# STM32WB55_Main_MCU.net
KiCad netlist of a schematic drawn in Altium Designer
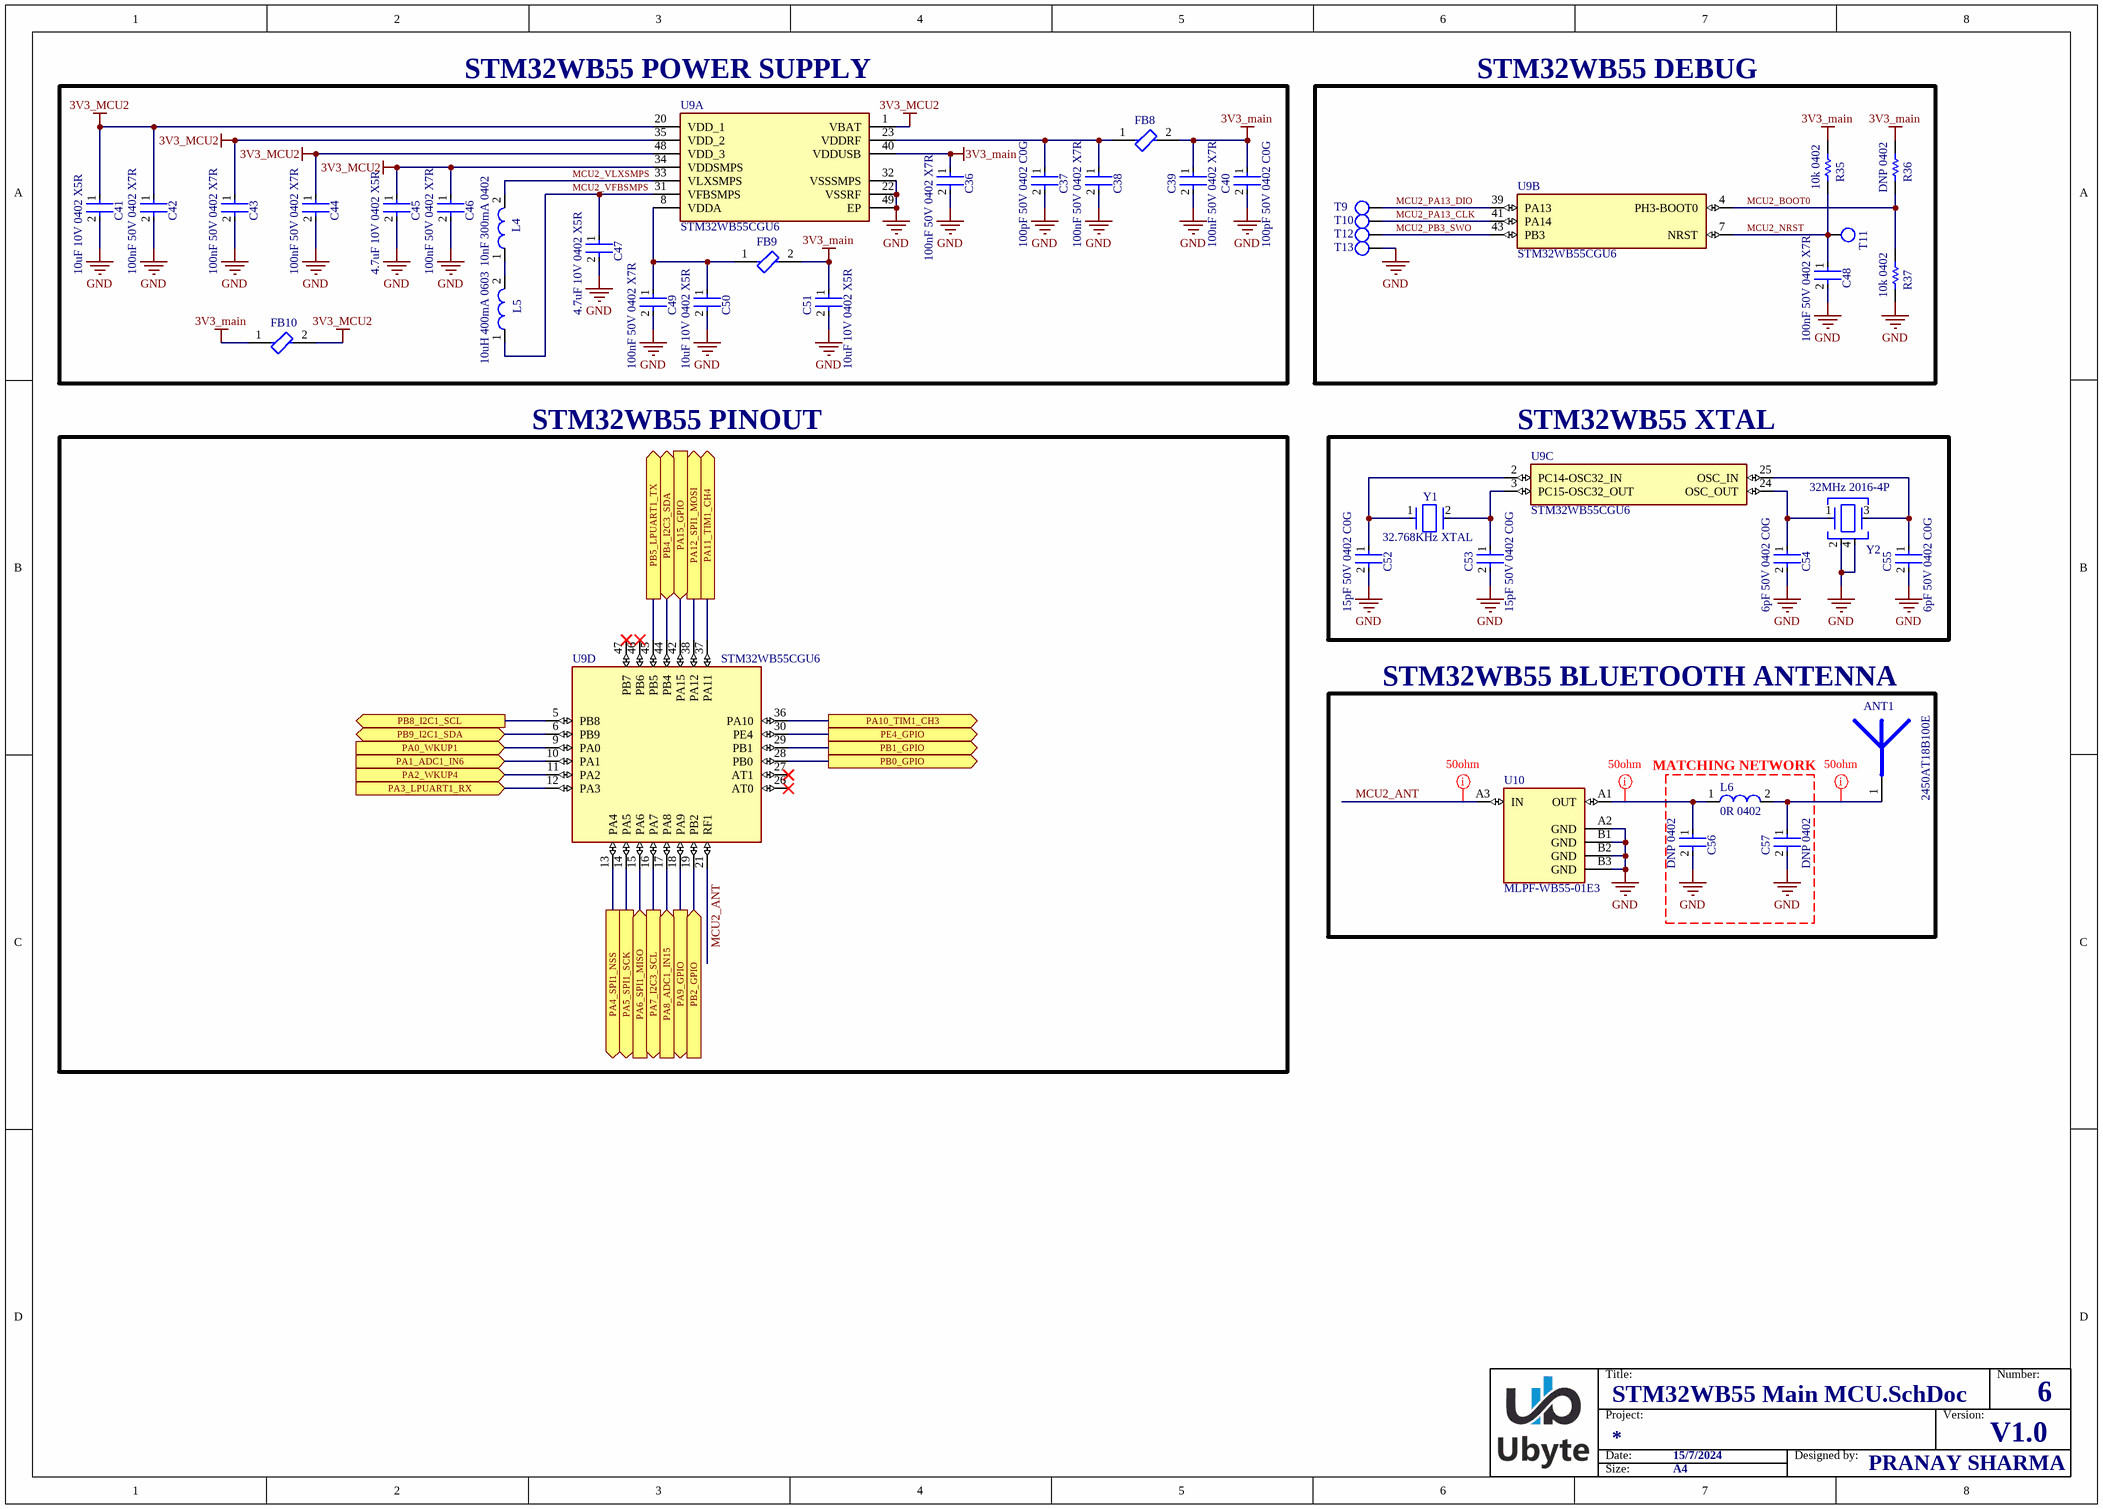
[diagram p0: STM32WB55 Main MCU.SchDoc]

(export (version "E")
  (design (tool "Eeschema 10.0.6"))
  (components
    (comp (ref "ANT1")
      (value "2450AT18B100E")
      (footprint "Miscellaneous_Lib:2450AT18B100E IPC-C")
      (libsource (lib "Miscellaneous_Lib") (part "2450AT18B100E"))
    )
    (comp (ref "C36")
      (value "100nF 50V 0402 X7R")
      (footprint "Res, Cap, Ind, LED, FB_Lib:0402 IPC CLASS C CAPACITOR")
      (libsource (lib "Capacitor_Lib") (part "100nF 50V 0402 X7R"))
    )
    (comp (ref "C37")
      (value "100pF 50V 0402 C0G")
      (footprint "Res, Cap, Ind, LED, FB_Lib:0402 IPC CLASS C CAPACITOR")
      (libsource (lib "Capacitor_Lib") (part "100pF 50V 0402 C0G"))
    )
    (comp (ref "C38")
      (value "100nF 50V 0402 X7R")
      (footprint "Res, Cap, Ind, LED, FB_Lib:0402 IPC CLASS C CAPACITOR")
      (libsource (lib "Capacitor_Lib") (part "100nF 50V 0402 X7R"))
    )
    (comp (ref "C39")
      (value "100nF 50V 0402 X7R")
      (footprint "Res, Cap, Ind, LED, FB_Lib:0402 IPC CLASS C CAPACITOR")
      (libsource (lib "Capacitor_Lib") (part "100nF 50V 0402 X7R"))
    )
    (comp (ref "C40")
      (value "100pF 50V 0402 C0G")
      (footprint "Res, Cap, Ind, LED, FB_Lib:0402 IPC CLASS C CAPACITOR")
      (libsource (lib "Capacitor_Lib") (part "100pF 50V 0402 C0G"))
    )
    (comp (ref "C41")
      (value "10uF 10V 0402 X5R")
      (footprint "Res, Cap, Ind, LED, FB_Lib:0402 IPC CLASS C CAPACITOR")
      (libsource (lib "Capacitor_Lib") (part "10uF 10V 0402 X5R"))
    )
    (comp (ref "C42")
      (value "100nF 50V 0402 X7R")
      (footprint "Res, Cap, Ind, LED, FB_Lib:0402 IPC CLASS C CAPACITOR")
      (libsource (lib "Capacitor_Lib") (part "100nF 50V 0402 X7R"))
    )
    (comp (ref "C43")
      (value "100nF 50V 0402 X7R")
      (footprint "Res, Cap, Ind, LED, FB_Lib:0402 IPC CLASS C CAPACITOR")
      (libsource (lib "Capacitor_Lib") (part "100nF 50V 0402 X7R"))
    )
    (comp (ref "C44")
      (value "100nF 50V 0402 X7R")
      (footprint "Res, Cap, Ind, LED, FB_Lib:0402 IPC CLASS C CAPACITOR")
      (libsource (lib "Capacitor_Lib") (part "100nF 50V 0402 X7R"))
    )
    (comp (ref "C45")
      (value "4.7uF 10V 0402 X5R")
      (footprint "Res, Cap, Ind, LED, FB_Lib:0402 IPC CLASS C CAPACITOR")
      (libsource (lib "Capacitor_Lib") (part "4.7uF 10V 0402 X5R"))
    )
    (comp (ref "C46")
      (value "100nF 50V 0402 X7R")
      (footprint "Res, Cap, Ind, LED, FB_Lib:0402 IPC CLASS C CAPACITOR")
      (libsource (lib "Capacitor_Lib") (part "100nF 50V 0402 X7R"))
    )
    (comp (ref "C47")
      (value "4.7uF 10V 0402 X5R")
      (footprint "Res, Cap, Ind, LED, FB_Lib:0402 IPC CLASS C CAPACITOR")
      (libsource (lib "Capacitor_Lib") (part "4.7uF 10V 0402 X5R"))
    )
    (comp (ref "C48")
      (value "100nF 50V 0402 X7R")
      (footprint "Res, Cap, Ind, LED, FB_Lib:0402 IPC CLASS C CAPACITOR")
      (libsource (lib "Capacitor_Lib") (part "100nF 50V 0402 X7R"))
    )
    (comp (ref "C49")
      (value "100nF 50V 0402 X7R")
      (footprint "Res, Cap, Ind, LED, FB_Lib:0402 IPC CLASS C CAPACITOR")
      (libsource (lib "Capacitor_Lib") (part "100nF 50V 0402 X7R"))
    )
    (comp (ref "C50")
      (value "10uF 10V 0402 X5R")
      (footprint "Res, Cap, Ind, LED, FB_Lib:0402 IPC CLASS C CAPACITOR")
      (libsource (lib "Capacitor_Lib") (part "10uF 10V 0402 X5R"))
    )
    (comp (ref "C51")
      (value "10uF 10V 0402 X5R")
      (footprint "Res, Cap, Ind, LED, FB_Lib:0402 IPC CLASS C CAPACITOR")
      (libsource (lib "Capacitor_Lib") (part "10uF 10V 0402 X5R"))
    )
    (comp (ref "C52")
      (value "15pF 50V 0402 C0G")
      (footprint "Res, Cap, Ind, LED, FB_Lib:0402 IPC CLASS C CAPACITOR")
      (libsource (lib "Capacitor_Lib") (part "15pF 50V 0402 C0G"))
    )
    (comp (ref "C53")
      (value "15pF 50V 0402 C0G")
      (footprint "Res, Cap, Ind, LED, FB_Lib:0402 IPC CLASS C CAPACITOR")
      (libsource (lib "Capacitor_Lib") (part "15pF 50V 0402 C0G"))
    )
    (comp (ref "C54")
      (value "6pF 50V 0402 C0G")
      (footprint "Res, Cap, Ind, LED, FB_Lib:0402 IPC CLASS C CAPACITOR")
      (libsource (lib "Capacitor_Lib") (part "6pF 50V 0402 C0G"))
    )
    (comp (ref "C55")
      (value "6pF 50V 0402 C0G")
      (footprint "Res, Cap, Ind, LED, FB_Lib:0402 IPC CLASS C CAPACITOR")
      (libsource (lib "Capacitor_Lib") (part "6pF 50V 0402 C0G"))
    )
    (comp (ref "C56")
      (value "DNP 0402")
      (footprint "Res, Cap, Ind, LED, FB_Lib:0402 IPC CLASS C CAPACITOR")
      (libsource (lib "Capacitor_Lib") (part "100nF 50V 0402 X7R"))
    )
    (comp (ref "C57")
      (value "DNP 0402")
      (footprint "Res, Cap, Ind, LED, FB_Lib:0402 IPC CLASS C CAPACITOR")
      (libsource (lib "Capacitor_Lib") (part "100nF 50V 0402 X7R"))
    )
    (comp (ref "FB8")
      (value "BLM15AX102SN1D")
      (footprint "Res, Cap, Ind, LED, FB_Lib:0402 IPC CLASS C FERRITE BEAD")
      (libsource (lib "Ferrite_Bead_Lib") (part "BLM15AX102SN1D"))
    )
    (comp (ref "FB9")
      (value "BLM15AX102SN1D")
      (footprint "Res, Cap, Ind, LED, FB_Lib:0402 IPC CLASS C FERRITE BEAD")
      (libsource (lib "Ferrite_Bead_Lib") (part "BLM15AX102SN1D"))
    )
    (comp (ref "FB10")
      (value "BLM15AX102SN1D")
      (footprint "Res, Cap, Ind, LED, FB_Lib:0402 IPC CLASS C FERRITE BEAD")
      (libsource (lib "Ferrite_Bead_Lib") (part "BLM15AX102SN1D"))
    )
    (comp (ref "L4")
      (value "10nF 300mA 0402")
      (footprint "Res, Cap, Ind, LED, FB_Lib:0402 IPC CLASS C FERRITE BEAD")
      (libsource (lib "Inductor_Lib") (part "SDCL1005C10NJTDF"))
    )
    (comp (ref "L5")
      (value "10uH 400mA 0603")
      (footprint "Res, Cap, Ind, LED, FB_Lib:0603 IPC CLASS C INDUCTOR")
      (libsource (lib "Inductor_Lib") (part "MGFL1608F100MT-LF"))
    )
    (comp (ref "L6")
      (value "0R 0402")
      (footprint "Res, Cap, Ind, LED, FB_Lib:0402 IPC CLASS C FERRITE BEAD")
      (libsource (lib "Inductor_Lib") (part "SDCL1005C10NJTDF"))
    )
    (comp (ref "R35")
      (value "10k 0402")
      (footprint "Res, Cap, Ind, LED, FB_Lib:0402 IPC CLASS C RESISTOR")
      (libsource (lib "Resistor_Lib") (part "10k 1% 0402"))
    )
    (comp (ref "R36")
      (value "DNP 0402")
      (footprint "Res, Cap, Ind, LED, FB_Lib:0402 IPC CLASS C RESISTOR")
      (libsource (lib "Resistor_Lib") (part "0R 1% 0402"))
    )
    (comp (ref "R37")
      (value "10k 0402")
      (footprint "Res, Cap, Ind, LED, FB_Lib:0402 IPC CLASS C RESISTOR")
      (libsource (lib "Resistor_Lib") (part "10k 1% 0402"))
    )
    (comp (ref "T9")
      (value "Test Point TH")
      (footprint "Miscellaneous_Lib:Test Point TH")
      (libsource (lib "Miscellaneous_Lib") (part "Test Point TH"))
    )
    (comp (ref "T10")
      (value "Test Point TH")
      (footprint "Miscellaneous_Lib:Test Point TH")
      (libsource (lib "Miscellaneous_Lib") (part "Test Point TH"))
    )
    (comp (ref "T11")
      (value "Test Point TH")
      (footprint "Miscellaneous_Lib:Test Point TH")
      (libsource (lib "Miscellaneous_Lib") (part "Test Point TH"))
    )
    (comp (ref "T12")
      (value "Test Point TH")
      (footprint "Miscellaneous_Lib:Test Point TH")
      (libsource (lib "Miscellaneous_Lib") (part "Test Point TH"))
    )
    (comp (ref "T13")
      (value "Test Point TH")
      (footprint "Miscellaneous_Lib:Test Point TH")
      (libsource (lib "Miscellaneous_Lib") (part "Test Point TH"))
    )
    (comp (ref "U9")
      (value "STM32WB55CGU6")
      (footprint "MCU_MPU_Lib:UFQFPN48 IPC-C")
      (libsource (lib "MCU_MPU_Lib") (part "STM32WB55CGU6"))
    )
    (comp (ref "U10")
      (value "MLPF-WB55-01E3")
      (footprint "Miscellaneous_Lib:MLPF-WB55-01E3")
      (libsource (lib "Miscellaneous_Lib") (part "MLPF-WB55-01E3"))
    )
    (comp (ref "Y1")
      (value "32.768KHz XTAL")
      (footprint "Crystals_and_Oscillators_Lib:SMD3215-2P IPC-C")
      (libsource (lib "Crystals_and_Oscillators_Lib") (part "H31003271C2070CY"))
    )
    (comp (ref "Y2")
      (value "32MHz 2016-4P")
      (footprint "Crystals_and_Oscillators_Lib:SMD2016-4P IPC-C")
      (libsource (lib "Crystals_and_Oscillators_Lib") (part "32MHz 2016-4P"))
    )
  )
  (nets
    (net (code "1") (name "/MCU2_ANT") (class "Default")
      (node (ref "U10") (pin "A3") (pinfunction "IN_A3") (pintype "bidirectional"))
      (node (ref "U9") (pin "21") (pinfunction "RF1_21") (pintype "bidirectional"))
    )
    (net (code "2") (name "/MCU2_BOOT0") (class "Default")
      (node (ref "R36") (pin "1") (pinfunction "1_1") (pintype "passive"))
      (node (ref "R37") (pin "2") (pinfunction "2_2") (pintype "passive"))
      (node (ref "U9") (pin "4") (pinfunction "PH3-BOOT0_4") (pintype "bidirectional"))
    )
    (net (code "3") (name "/MCU2_NRST") (class "Default")
      (node (ref "C48") (pin "1") (pinfunction "1_1") (pintype "passive"))
      (node (ref "R35") (pin "1") (pinfunction "1_1") (pintype "passive"))
      (node (ref "T11") (pin "0") (pinfunction "0_0") (pintype "passive"))
      (node (ref "U9") (pin "7") (pinfunction "NRST_7") (pintype "bidirectional"))
    )
    (net (code "4") (name "/MCU2_PA13_CLK") (class "Default")
      (node (ref "T10") (pin "0") (pinfunction "0_0") (pintype "passive"))
      (node (ref "U9") (pin "41") (pinfunction "PA14_41") (pintype "bidirectional"))
    )
    (net (code "5") (name "/MCU2_PA13_DIO") (class "Default")
      (node (ref "T9") (pin "0") (pinfunction "0_0") (pintype "passive"))
      (node (ref "U9") (pin "39") (pinfunction "PA13_39") (pintype "bidirectional"))
    )
    (net (code "6") (name "/MCU2_PB3_SWO") (class "Default")
      (node (ref "T12") (pin "0") (pinfunction "0_0") (pintype "passive"))
      (node (ref "U9") (pin "43") (pinfunction "PB3_43") (pintype "bidirectional"))
    )
    (net (code "7") (name "/MCU2_VFBSMPS") (class "Default")
      (node (ref "C47") (pin "1") (pinfunction "1_1") (pintype "passive"))
      (node (ref "L5") (pin "1") (pinfunction "1_1") (pintype "passive"))
      (node (ref "U9") (pin "31") (pinfunction "VFBSMPS_31") (pintype "power_in"))
    )
    (net (code "8") (name "/MCU2_VLXSMPS") (class "Default")
      (node (ref "L4") (pin "2") (pinfunction "2_2") (pintype "passive"))
      (node (ref "U9") (pin "33") (pinfunction "VLXSMPS_33") (pintype "power_in"))
    )
    (net (code "9") (name "/PA0_WKUP1") (class "Default")
      (node (ref "U9") (pin "9") (pinfunction "PA0_9") (pintype "bidirectional"))
    )
    (net (code "10") (name "/PA1_ADC1_IN6") (class "Default")
      (node (ref "U9") (pin "10") (pinfunction "PA1_10") (pintype "bidirectional"))
    )
    (net (code "11") (name "/PA2_WKUP4") (class "Default")
      (node (ref "U9") (pin "11") (pinfunction "PA2_11") (pintype "bidirectional"))
    )
    (net (code "12") (name "/PA3_LPUART1_RX") (class "Default")
      (node (ref "U9") (pin "12") (pinfunction "PA3_12") (pintype "bidirectional"))
    )
    (net (code "13") (name "/PA4_SPI1_NSS") (class "Default")
      (node (ref "U9") (pin "13") (pinfunction "PA4_13") (pintype "bidirectional"))
    )
    (net (code "14") (name "/PA5_SPI1_SCK") (class "Default")
      (node (ref "U9") (pin "14") (pinfunction "PA5_14") (pintype "bidirectional"))
    )
    (net (code "15") (name "/PA6_SPI1_MISO") (class "Default")
      (node (ref "U9") (pin "15") (pinfunction "PA6_15") (pintype "bidirectional"))
    )
    (net (code "16") (name "/PA7_I2C3_SCL") (class "Default")
      (node (ref "U9") (pin "16") (pinfunction "PA7_16") (pintype "bidirectional"))
    )
    (net (code "17") (name "/PA8_ADC1_IN15") (class "Default")
      (node (ref "U9") (pin "17") (pinfunction "PA8_17") (pintype "bidirectional"))
    )
    (net (code "18") (name "/PA9_GPIO") (class "Default")
      (node (ref "U9") (pin "18") (pinfunction "PA9_18") (pintype "bidirectional"))
    )
    (net (code "19") (name "/PA10_TIM1_CH3") (class "Default")
      (node (ref "U9") (pin "36") (pinfunction "PA10_36") (pintype "bidirectional"))
    )
    (net (code "20") (name "/PA11_TIM1_CH4") (class "Default")
      (node (ref "U9") (pin "37") (pinfunction "PA11_37") (pintype "bidirectional"))
    )
    (net (code "21") (name "/PA12_SPI1_MOSI") (class "Default")
      (node (ref "U9") (pin "38") (pinfunction "PA12_38") (pintype "bidirectional"))
    )
    (net (code "22") (name "/PA15_GPIO") (class "Default")
      (node (ref "U9") (pin "42") (pinfunction "PA15_42") (pintype "bidirectional"))
    )
    (net (code "23") (name "/PB0_GPIO") (class "Default")
      (node (ref "U9") (pin "28") (pinfunction "PB0_28") (pintype "bidirectional"))
    )
    (net (code "24") (name "/PB1_GPIO") (class "Default")
      (node (ref "U9") (pin "29") (pinfunction "PB1_29") (pintype "bidirectional"))
    )
    (net (code "25") (name "/PB2_GPIO") (class "Default")
      (node (ref "U9") (pin "19") (pinfunction "PB2_19") (pintype "bidirectional"))
    )
    (net (code "26") (name "/PB4_I2C3_SDA") (class "Default")
      (node (ref "U9") (pin "44") (pinfunction "PB4_44") (pintype "bidirectional"))
    )
    (net (code "27") (name "/PB5_LPUART1_TX") (class "Default")
      (node (ref "U9") (pin "45") (pinfunction "PB5_45") (pintype "bidirectional"))
    )
    (net (code "28") (name "/PB8_I2C1_SCL") (class "Default")
      (node (ref "U9") (pin "5") (pinfunction "PB8_5") (pintype "bidirectional"))
    )
    (net (code "29") (name "/PB9_I2C1_SDA") (class "Default")
      (node (ref "U9") (pin "6") (pinfunction "PB9_6") (pintype "bidirectional"))
    )
    (net (code "30") (name "/PE4_GPIO") (class "Default")
      (node (ref "U9") (pin "30") (pinfunction "PE4_30") (pintype "bidirectional"))
    )
    (net (code "31") (name "3V3_MCU2") (class "Default")
      (node (ref "C41") (pin "1") (pinfunction "1_1") (pintype "passive"))
      (node (ref "C42") (pin "1") (pinfunction "1_1") (pintype "passive"))
      (node (ref "C43") (pin "1") (pinfunction "1_1") (pintype "passive"))
      (node (ref "C44") (pin "1") (pinfunction "1_1") (pintype "passive"))
      (node (ref "C45") (pin "1") (pinfunction "1_1") (pintype "passive"))
      (node (ref "C46") (pin "1") (pinfunction "1_1") (pintype "passive"))
      (node (ref "FB10") (pin "2") (pinfunction "2_2") (pintype "passive"))
      (node (ref "U9") (pin "1") (pinfunction "VBAT_1") (pintype "power_in"))
      (node (ref "U9") (pin "20") (pinfunction "VDD_1_20") (pintype "power_in"))
      (node (ref "U9") (pin "34") (pinfunction "VDDSMPS_34") (pintype "power_in"))
      (node (ref "U9") (pin "35") (pinfunction "VDD_2_35") (pintype "power_in"))
      (node (ref "U9") (pin "48") (pinfunction "VDD_3_48") (pintype "power_in"))
    )
    (net (code "32") (name "3V3_main") (class "Default")
      (node (ref "C36") (pin "1") (pinfunction "1_1") (pintype "passive"))
      (node (ref "C39") (pin "1") (pinfunction "1_1") (pintype "passive"))
      (node (ref "C40") (pin "1") (pinfunction "1_1") (pintype "passive"))
      (node (ref "C51") (pin "1") (pinfunction "1_1") (pintype "passive"))
      (node (ref "FB10") (pin "1") (pinfunction "1_1") (pintype "passive"))
      (node (ref "FB8") (pin "2") (pinfunction "2_2") (pintype "passive"))
      (node (ref "FB9") (pin "2") (pinfunction "2_2") (pintype "passive"))
      (node (ref "R35") (pin "2") (pinfunction "2_2") (pintype "passive"))
      (node (ref "R36") (pin "2") (pinfunction "2_2") (pintype "passive"))
      (node (ref "U9") (pin "40") (pinfunction "VDDUSB_40") (pintype "power_in"))
    )
    (net (code "33") (name "GND") (class "Default")
      (node (ref "C36") (pin "2") (pinfunction "2_2") (pintype "passive"))
      (node (ref "C37") (pin "2") (pinfunction "2_2") (pintype "passive"))
      (node (ref "C38") (pin "2") (pinfunction "2_2") (pintype "passive"))
      (node (ref "C39") (pin "2") (pinfunction "2_2") (pintype "passive"))
      (node (ref "C40") (pin "2") (pinfunction "2_2") (pintype "passive"))
      (node (ref "C41") (pin "2") (pinfunction "2_2") (pintype "passive"))
      (node (ref "C42") (pin "2") (pinfunction "2_2") (pintype "passive"))
      (node (ref "C43") (pin "2") (pinfunction "2_2") (pintype "passive"))
      (node (ref "C44") (pin "2") (pinfunction "2_2") (pintype "passive"))
      (node (ref "C45") (pin "2") (pinfunction "2_2") (pintype "passive"))
      (node (ref "C46") (pin "2") (pinfunction "2_2") (pintype "passive"))
      (node (ref "C47") (pin "2") (pinfunction "2_2") (pintype "passive"))
      (node (ref "C48") (pin "2") (pinfunction "2_2") (pintype "passive"))
      (node (ref "C49") (pin "2") (pinfunction "2_2") (pintype "passive"))
      (node (ref "C50") (pin "2") (pinfunction "2_2") (pintype "passive"))
      (node (ref "C51") (pin "2") (pinfunction "2_2") (pintype "passive"))
      (node (ref "C52") (pin "2") (pinfunction "2_2") (pintype "passive"))
      (node (ref "C53") (pin "2") (pinfunction "2_2") (pintype "passive"))
      (node (ref "C54") (pin "2") (pinfunction "2_2") (pintype "passive"))
      (node (ref "C55") (pin "2") (pinfunction "2_2") (pintype "passive"))
      (node (ref "C56") (pin "2") (pinfunction "2_2") (pintype "passive"))
      (node (ref "C57") (pin "2") (pinfunction "2_2") (pintype "passive"))
      (node (ref "R37") (pin "1") (pinfunction "1_1") (pintype "passive"))
      (node (ref "T13") (pin "0") (pinfunction "0_0") (pintype "passive"))
      (node (ref "U10") (pin "A2") (pinfunction "GND_A2") (pintype "power_in"))
      (node (ref "U10") (pin "B1") (pinfunction "GND_B1") (pintype "power_in"))
      (node (ref "U10") (pin "B2") (pinfunction "GND_B2") (pintype "power_in"))
      (node (ref "U10") (pin "B3") (pinfunction "GND_B3") (pintype "power_in"))
      (node (ref "U9") (pin "22") (pinfunction "VSSRF_22") (pintype "power_in"))
      (node (ref "U9") (pin "32") (pinfunction "VSSSMPS_32") (pintype "power_in"))
      (node (ref "U9") (pin "49") (pinfunction "EP_49") (pintype "power_in"))
      (node (ref "Y2") (pin "2") (pinfunction "2_2") (pintype "passive"))
      (node (ref "Y2") (pin "4") (pinfunction "4_4") (pintype "passive"))
    )
    (net (code "34") (name "Net-(ANT1-Pad1)") (class "Default")
      (node (ref "ANT1") (pin "1") (pinfunction "1_1") (pintype "passive"))
      (node (ref "C57") (pin "1") (pinfunction "1_1") (pintype "passive"))
      (node (ref "L6") (pin "2") (pinfunction "2_2") (pintype "passive"))
    )
    (net (code "35") (name "Net-(L4-Pad1)") (class "Default")
      (node (ref "L4") (pin "1") (pinfunction "1_1") (pintype "passive"))
      (node (ref "L5") (pin "2") (pinfunction "2_2") (pintype "passive"))
    )
    (net (code "36") (name "Net-(U9A-VDDA)") (class "Default")
      (node (ref "C49") (pin "1") (pinfunction "1_1") (pintype "passive"))
      (node (ref "C50") (pin "1") (pinfunction "1_1") (pintype "passive"))
      (node (ref "FB9") (pin "1") (pinfunction "1_1") (pintype "passive"))
      (node (ref "U9") (pin "8") (pinfunction "VDDA_8") (pintype "power_in"))
    )
    (net (code "37") (name "Net-(U9A-VDDRF)") (class "Default")
      (node (ref "C37") (pin "1") (pinfunction "1_1") (pintype "passive"))
      (node (ref "C38") (pin "1") (pinfunction "1_1") (pintype "passive"))
      (node (ref "FB8") (pin "1") (pinfunction "1_1") (pintype "passive"))
      (node (ref "U9") (pin "23") (pinfunction "VDDRF_23") (pintype "power_in"))
    )
    (net (code "38") (name "Net-(U9C-OSC_IN)") (class "Default")
      (node (ref "C55") (pin "1") (pinfunction "1_1") (pintype "passive"))
      (node (ref "U9") (pin "25") (pinfunction "OSC_IN_25") (pintype "bidirectional"))
      (node (ref "Y2") (pin "3") (pinfunction "2_3") (pintype "passive"))
    )
    (net (code "39") (name "Net-(U9C-OSC_OUT)") (class "Default")
      (node (ref "C54") (pin "1") (pinfunction "1_1") (pintype "passive"))
      (node (ref "U9") (pin "24") (pinfunction "OSC_OUT_24") (pintype "bidirectional"))
      (node (ref "Y2") (pin "1") (pinfunction "1_1") (pintype "passive"))
    )
    (net (code "40") (name "Net-(U9C-PC14-OSC32_IN)") (class "Default")
      (node (ref "C52") (pin "1") (pinfunction "1_1") (pintype "passive"))
      (node (ref "U9") (pin "2") (pinfunction "PC14-OSC32_IN_2") (pintype "bidirectional"))
      (node (ref "Y1") (pin "1") (pinfunction "1_1") (pintype "passive"))
    )
    (net (code "41") (name "Net-(U9C-PC15-OSC32_OUT)") (class "Default")
      (node (ref "C53") (pin "1") (pinfunction "1_1") (pintype "passive"))
      (node (ref "U9") (pin "3") (pinfunction "PC15-OSC32_OUT_3") (pintype "bidirectional"))
      (node (ref "Y1") (pin "2") (pinfunction "2_2") (pintype "passive"))
    )
    (net (code "42") (name "Net-(U10-OUT)") (class "Default")
      (node (ref "C56") (pin "1") (pinfunction "1_1") (pintype "passive"))
      (node (ref "L6") (pin "1") (pinfunction "1_1") (pintype "passive"))
      (node (ref "U10") (pin "A1") (pinfunction "OUT_A1") (pintype "bidirectional"))
    )
    (net (code "43") (name "unconnected-(U9D-AT0-Pad26)") (class "Default")
      (node (ref "U9") (pin "26") (pinfunction "AT0_26") (pintype "bidirectional+no_connect"))
    )
    (net (code "44") (name "unconnected-(U9D-AT1-Pad27)") (class "Default")
      (node (ref "U9") (pin "27") (pinfunction "AT1_27") (pintype "bidirectional+no_connect"))
    )
    (net (code "45") (name "unconnected-(U9D-PB6-Pad46)") (class "Default")
      (node (ref "U9") (pin "46") (pinfunction "PB6_46") (pintype "bidirectional+no_connect"))
    )
    (net (code "46") (name "unconnected-(U9D-PB7-Pad47)") (class "Default")
      (node (ref "U9") (pin "47") (pinfunction "PB7_47") (pintype "bidirectional+no_connect"))
    )
  )
)
